# BLDC_PMSM.net
KiCad netlist of a schematic drawn in EAGLE
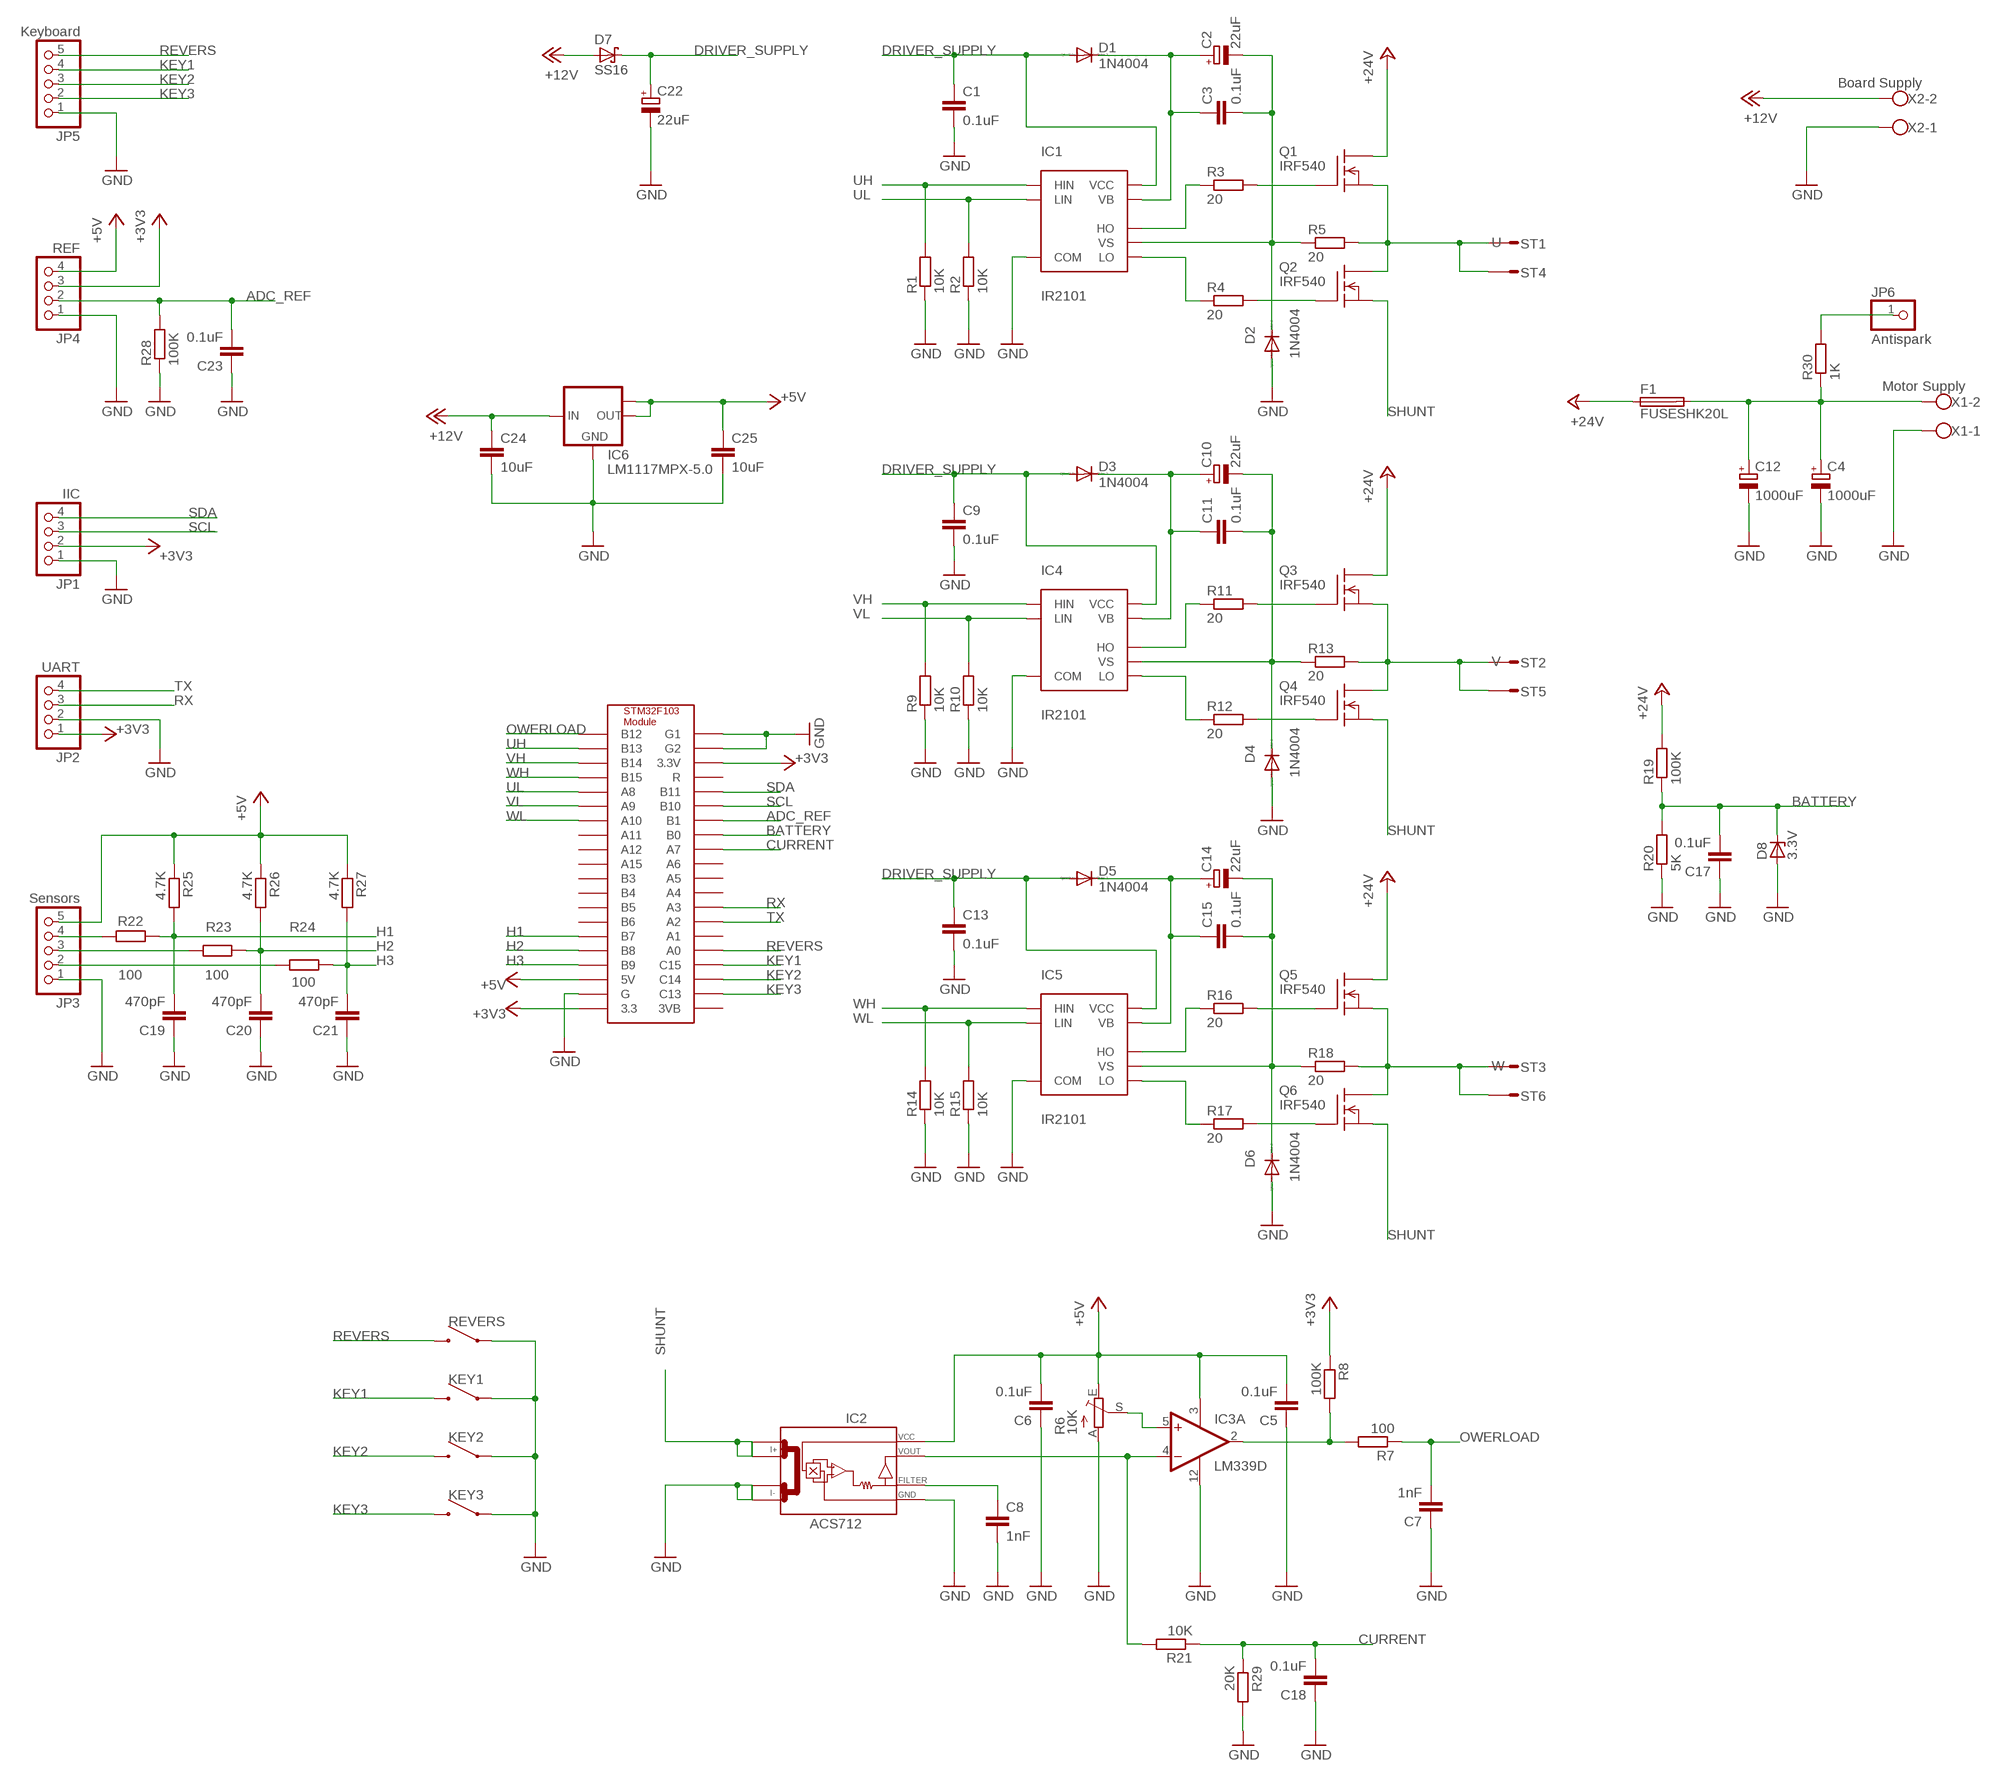
[diagram p0: schematic, sheet 1]

(export (version "E")
  (design (tool "Eeschema 10.0.6"))
  (components
    (comp (ref "C1")
      (value "0.1uF")
      (footprint "eagle-import:C0805K")
      (libsource (lib "eagle-import") (part "C-EUC0805K"))
    )
    (comp (ref "C2")
      (value "22uF")
      (footprint "eagle-import:E2-5")
      (libsource (lib "eagle-import") (part "CPOL-EUE2-5"))
    )
    (comp (ref "C3")
      (value "0.1uF")
      (footprint "eagle-import:C0805K")
      (libsource (lib "eagle-import") (part "C-EUC0805K"))
    )
    (comp (ref "C4")
      (value "1000uF")
      (footprint "eagle-import:E5-13")
      (libsource (lib "eagle-import") (part "CPOL-EUE5-13"))
    )
    (comp (ref "C5")
      (value "0.1uF")
      (footprint "eagle-import:C0805K")
      (libsource (lib "eagle-import") (part "C-EUC0805K"))
    )
    (comp (ref "C6")
      (value "0.1uF")
      (footprint "eagle-import:C0805K")
      (libsource (lib "eagle-import") (part "C-EUC0805K"))
    )
    (comp (ref "C7")
      (value "1nF")
      (footprint "eagle-import:C0805K")
      (libsource (lib "eagle-import") (part "C-EUC0805K"))
    )
    (comp (ref "C8")
      (value "1nF")
      (footprint "eagle-import:C0805K")
      (libsource (lib "eagle-import") (part "C-EUC0805K"))
    )
    (comp (ref "C9")
      (value "0.1uF")
      (footprint "eagle-import:C0805K")
      (libsource (lib "eagle-import") (part "C-EUC0805K"))
    )
    (comp (ref "C10")
      (value "22uF")
      (footprint "eagle-import:E2-5")
      (libsource (lib "eagle-import") (part "CPOL-EUE2-5"))
    )
    (comp (ref "C11")
      (value "0.1uF")
      (footprint "eagle-import:C0805K")
      (libsource (lib "eagle-import") (part "C-EUC0805K"))
    )
    (comp (ref "C12")
      (value "1000uF")
      (footprint "eagle-import:E5-13")
      (libsource (lib "eagle-import") (part "CPOL-EUE5-13"))
    )
    (comp (ref "C13")
      (value "0.1uF")
      (footprint "eagle-import:C0805K")
      (libsource (lib "eagle-import") (part "C-EUC0805K"))
    )
    (comp (ref "C14")
      (value "22uF")
      (footprint "eagle-import:E2-5")
      (libsource (lib "eagle-import") (part "CPOL-EUE2-5"))
    )
    (comp (ref "C15")
      (value "0.1uF")
      (footprint "eagle-import:C0805K")
      (libsource (lib "eagle-import") (part "C-EUC0805K"))
    )
    (comp (ref "C17")
      (value "0.1uF")
      (footprint "eagle-import:C0805K")
      (libsource (lib "eagle-import") (part "C-EUC0805K"))
    )
    (comp (ref "C18")
      (value "0.1uF")
      (footprint "eagle-import:C0805K")
      (libsource (lib "eagle-import") (part "C-EUC0805K"))
    )
    (comp (ref "C19")
      (value "470pF")
      (footprint "eagle-import:C0805K")
      (libsource (lib "eagle-import") (part "C-EUC0805K"))
    )
    (comp (ref "C20")
      (value "470pF")
      (footprint "eagle-import:C0805K")
      (libsource (lib "eagle-import") (part "C-EUC0805K"))
    )
    (comp (ref "C21")
      (value "470pF")
      (footprint "eagle-import:C0805K")
      (libsource (lib "eagle-import") (part "C-EUC0805K"))
    )
    (comp (ref "C22")
      (value "22uF")
      (footprint "eagle-import:E2-5")
      (libsource (lib "eagle-import") (part "CPOL-EUE2-5"))
    )
    (comp (ref "C23")
      (value "0.1uF")
      (footprint "eagle-import:C0805K")
      (libsource (lib "eagle-import") (part "C-EUC0805K"))
    )
    (comp (ref "C24")
      (value "10uF")
      (footprint "eagle-import:C0805K")
      (libsource (lib "eagle-import") (part "C-EUC0805K"))
    )
    (comp (ref "C25")
      (value "10uF")
      (footprint "eagle-import:C1206K")
      (libsource (lib "eagle-import") (part "C-EUC1206K"))
    )
    (comp (ref "D1")
      (value "1N4004")
      (footprint "eagle-import:DO41-10")
      (libsource (lib "eagle-import") (part "1N4004"))
    )
    (comp (ref "D2")
      (value "1N4004")
      (footprint "eagle-import:DO41-10")
      (libsource (lib "eagle-import") (part "1N4004"))
    )
    (comp (ref "D3")
      (value "1N4004")
      (footprint "eagle-import:DO41-10")
      (libsource (lib "eagle-import") (part "1N4004"))
    )
    (comp (ref "D4")
      (value "1N4004")
      (footprint "eagle-import:DO41-10")
      (libsource (lib "eagle-import") (part "1N4004"))
    )
    (comp (ref "D5")
      (value "1N4004")
      (footprint "eagle-import:DO41-10")
      (libsource (lib "eagle-import") (part "1N4004"))
    )
    (comp (ref "D6")
      (value "1N4004")
      (footprint "eagle-import:DO41-10")
      (libsource (lib "eagle-import") (part "1N4004"))
    )
    (comp (ref "D7")
      (value "SS16")
      (footprint "eagle-import:SMB")
      (libsource (lib "eagle-import") (part "SCHOTTKY-DIODESMD"))
    )
    (comp (ref "D8")
      (value "3.3V")
      (footprint "eagle-import:SMB")
      (libsource (lib "eagle-import") (part "ZENER-DIODESMB"))
    )
    (comp (ref "F1")
      (value "FUSESHK20L")
      (footprint "eagle-import:SHK20L")
      (libsource (lib "eagle-import") (part "FUSESHK20L"))
    )
    (comp (ref "IC1")
      (value "IR2101")
      (footprint "eagle-import:SO08")
      (libsource (lib "eagle-import") (part "IR2101S"))
    )
    (comp (ref "IC2")
      (value "ACS712")
      (footprint "eagle-import:SO08")
      (libsource (lib "eagle-import") (part "ACS712"))
    )
    (comp (ref "IC3")
      (value "LM339D")
      (footprint "eagle-import:SO14")
      (libsource (lib "eagle-import") (part "LM339D"))
    )
    (comp (ref "IC4")
      (value "IR2101")
      (footprint "eagle-import:SO08")
      (libsource (lib "eagle-import") (part "IR2101S"))
    )
    (comp (ref "IC5")
      (value "IR2101")
      (footprint "eagle-import:SO08")
      (libsource (lib "eagle-import") (part "IR2101S"))
    )
    (comp (ref "IC6")
      (value "LM1117MPX-5.0")
      (footprint "eagle-import:SOT223")
      (libsource (lib "eagle-import") (part "LM1117MPX-5.0"))
    )
    (comp (ref "JP1")
      (value "IIC")
      (footprint "eagle-import:1X04")
      (libsource (lib "eagle-import") (part "PINHD-1X4"))
    )
    (comp (ref "JP2")
      (value "UART")
      (footprint "eagle-import:1X04")
      (libsource (lib "eagle-import") (part "PINHD-1X4"))
    )
    (comp (ref "JP3")
      (value "Sensors")
      (footprint "eagle-import:1X05")
      (libsource (lib "eagle-import") (part "PINHD-1X5"))
    )
    (comp (ref "JP4")
      (value "REF")
      (footprint "eagle-import:1X04")
      (libsource (lib "eagle-import") (part "PINHD-1X4"))
    )
    (comp (ref "JP5")
      (value "Keyboard")
      (footprint "eagle-import:1X05")
      (libsource (lib "eagle-import") (part "PINHD-1X5"))
    )
    (comp (ref "JP6")
      (value "Antispark")
      (footprint "eagle-import:1X01")
      (libsource (lib "eagle-import") (part "PINHD-1X1"))
    )
    (comp (ref "KEY1")
      (value "SWITCH")
      (footprint "eagle-import:SWITCH")
      (libsource (lib "eagle-import") (part "SWITCH"))
    )
    (comp (ref "KEY2")
      (value "SWITCH")
      (footprint "eagle-import:SWITCH")
      (libsource (lib "eagle-import") (part "SWITCH"))
    )
    (comp (ref "KEY3")
      (value "SWITCH")
      (footprint "eagle-import:SWITCH")
      (libsource (lib "eagle-import") (part "SWITCH"))
    )
    (comp (ref "Q1")
      (value "IRF540")
      (footprint "eagle-import:TO220")
      (libsource (lib "eagle-import") (part "IRF540"))
    )
    (comp (ref "Q2")
      (value "IRF540")
      (footprint "eagle-import:TO220")
      (libsource (lib "eagle-import") (part "IRF540"))
    )
    (comp (ref "Q3")
      (value "IRF540")
      (footprint "eagle-import:TO220")
      (libsource (lib "eagle-import") (part "IRF540"))
    )
    (comp (ref "Q4")
      (value "IRF540")
      (footprint "eagle-import:TO220")
      (libsource (lib "eagle-import") (part "IRF540"))
    )
    (comp (ref "Q5")
      (value "IRF540")
      (footprint "eagle-import:TO220")
      (libsource (lib "eagle-import") (part "IRF540"))
    )
    (comp (ref "Q6")
      (value "IRF540")
      (footprint "eagle-import:TO220")
      (libsource (lib "eagle-import") (part "IRF540"))
    )
    (comp (ref "R1")
      (value "10K")
      (footprint "eagle-import:M0805")
      (libsource (lib "eagle-import") (part "R-EU_M0805"))
    )
    (comp (ref "R2")
      (value "10K")
      (footprint "eagle-import:M0805")
      (libsource (lib "eagle-import") (part "R-EU_M0805"))
    )
    (comp (ref "R3")
      (value "20")
      (footprint "eagle-import:M0805")
      (libsource (lib "eagle-import") (part "R-EU_M0805"))
    )
    (comp (ref "R4")
      (value "20")
      (footprint "eagle-import:M0805")
      (libsource (lib "eagle-import") (part "R-EU_M0805"))
    )
    (comp (ref "R5")
      (value "20")
      (footprint "eagle-import:M0805")
      (libsource (lib "eagle-import") (part "R-EU_M0805"))
    )
    (comp (ref "R6")
      (value "10K")
      (footprint "eagle-import:CA6V")
      (libsource (lib "eagle-import") (part "TRIM_EU-CA6V"))
    )
    (comp (ref "R7")
      (value "100")
      (footprint "eagle-import:M0805")
      (libsource (lib "eagle-import") (part "R-EU_M0805"))
    )
    (comp (ref "R8")
      (value "100K")
      (footprint "eagle-import:M0805")
      (libsource (lib "eagle-import") (part "R-EU_M0805"))
    )
    (comp (ref "R9")
      (value "10K")
      (footprint "eagle-import:M0805")
      (libsource (lib "eagle-import") (part "R-EU_M0805"))
    )
    (comp (ref "R10")
      (value "10K")
      (footprint "eagle-import:M0805")
      (libsource (lib "eagle-import") (part "R-EU_M0805"))
    )
    (comp (ref "R11")
      (value "20")
      (footprint "eagle-import:M0805")
      (libsource (lib "eagle-import") (part "R-EU_M0805"))
    )
    (comp (ref "R12")
      (value "20")
      (footprint "eagle-import:M0805")
      (libsource (lib "eagle-import") (part "R-EU_M0805"))
    )
    (comp (ref "R13")
      (value "20")
      (footprint "eagle-import:M0805")
      (libsource (lib "eagle-import") (part "R-EU_M0805"))
    )
    (comp (ref "R14")
      (value "10K")
      (footprint "eagle-import:M0805")
      (libsource (lib "eagle-import") (part "R-EU_M0805"))
    )
    (comp (ref "R15")
      (value "10K")
      (footprint "eagle-import:M0805")
      (libsource (lib "eagle-import") (part "R-EU_M0805"))
    )
    (comp (ref "R16")
      (value "20")
      (footprint "eagle-import:M0805")
      (libsource (lib "eagle-import") (part "R-EU_M0805"))
    )
    (comp (ref "R17")
      (value "20")
      (footprint "eagle-import:M0805")
      (libsource (lib "eagle-import") (part "R-EU_M0805"))
    )
    (comp (ref "R18")
      (value "20")
      (footprint "eagle-import:M0805")
      (libsource (lib "eagle-import") (part "R-EU_M0805"))
    )
    (comp (ref "R19")
      (value "100K")
      (footprint "eagle-import:M0805")
      (libsource (lib "eagle-import") (part "R-EU_M0805"))
    )
    (comp (ref "R20")
      (value "5K")
      (footprint "eagle-import:M0805")
      (libsource (lib "eagle-import") (part "R-EU_M0805"))
    )
    (comp (ref "R21")
      (value "10K")
      (footprint "eagle-import:M0805")
      (libsource (lib "eagle-import") (part "R-EU_M0805"))
    )
    (comp (ref "R22")
      (value "100")
      (footprint "eagle-import:M0805")
      (libsource (lib "eagle-import") (part "R-EU_M0805"))
    )
    (comp (ref "R23")
      (value "100")
      (footprint "eagle-import:M0805")
      (libsource (lib "eagle-import") (part "R-EU_M0805"))
    )
    (comp (ref "R24")
      (value "100")
      (footprint "eagle-import:M0805")
      (libsource (lib "eagle-import") (part "R-EU_M0805"))
    )
    (comp (ref "R25")
      (value "4.7K")
      (footprint "eagle-import:M0805")
      (libsource (lib "eagle-import") (part "R-EU_M0805"))
    )
    (comp (ref "R26")
      (value "4.7K")
      (footprint "eagle-import:M0805")
      (libsource (lib "eagle-import") (part "R-EU_M0805"))
    )
    (comp (ref "R27")
      (value "4.7K")
      (footprint "eagle-import:M0805")
      (libsource (lib "eagle-import") (part "R-EU_M0805"))
    )
    (comp (ref "R28")
      (value "100K")
      (footprint "eagle-import:M0805")
      (libsource (lib "eagle-import") (part "R-EU_M0805"))
    )
    (comp (ref "R29")
      (value "20K")
      (footprint "eagle-import:M0805")
      (libsource (lib "eagle-import") (part "R-EU_M0805"))
    )
    (comp (ref "R30")
      (value "1K")
      (footprint "eagle-import:M0805")
      (libsource (lib "eagle-import") (part "R-EU_M0805"))
    )
    (comp (ref "REVERS")
      (value "SWITCH")
      (footprint "eagle-import:SWITCH")
      (libsource (lib "eagle-import") (part "SWITCH"))
    )
    (comp (ref "ST1")
      (value "ST2,8")
      (footprint "eagle-import:ST2,8")
      (libsource (lib "eagle-import") (part "ST2,8"))
    )
    (comp (ref "ST2")
      (value "ST2,8")
      (footprint "eagle-import:ST2,8")
      (libsource (lib "eagle-import") (part "ST2,8"))
    )
    (comp (ref "ST3")
      (value "ST2,8")
      (footprint "eagle-import:ST2,8")
      (libsource (lib "eagle-import") (part "ST2,8"))
    )
    (comp (ref "ST4")
      (value "ST2,8")
      (footprint "eagle-import:ST2,8")
      (libsource (lib "eagle-import") (part "ST2,8"))
    )
    (comp (ref "ST5")
      (value "ST2,8")
      (footprint "eagle-import:ST2,8")
      (libsource (lib "eagle-import") (part "ST2,8"))
    )
    (comp (ref "ST6")
      (value "ST2,8")
      (footprint "eagle-import:ST2,8")
      (libsource (lib "eagle-import") (part "ST2,8"))
    )
    (comp (ref "U$1")
      (value "STM32F103MODULE")
      (footprint "eagle-import:STM32F103MODULE")
      (libsource (lib "eagle-import") (part "STM32F103MODULE"))
    )
    (comp (ref "X1")
      (value "Motor Supply")
      (footprint "eagle-import:W237-102")
      (fields (field (name "MPN") "237-102"))
      (libsource (lib "eagle-import") (part "W237-102"))
    )
    (comp (ref "X2")
      (value "Board Supply")
      (footprint "eagle-import:W237-102")
      (fields (field (name "MPN") "237-102"))
      (libsource (lib "eagle-import") (part "W237-102"))
    )
  )
  (nets
    (net (code "1") (name "+3V3") (class "Default")
      (node (ref "JP1") (pin "2") (pinfunction "2_2") (pintype "passive"))
      (node (ref "JP2") (pin "1") (pinfunction "1_1") (pintype "passive"))
      (node (ref "JP4") (pin "3") (pinfunction "3_3") (pintype "passive"))
      (node (ref "R8") (pin "1") (pinfunction "1_1") (pintype "passive"))
      (node (ref "U$1") (pin "P$20") (pinfunction "3.3_P$20") (pintype "power_in"))
      (node (ref "U$1") (pin "P$23") (pinfunction "3.3V_P$23") (pintype "power_in"))
    )
    (net (code "2") (name "+5V") (class "Default")
      (node (ref "C25") (pin "1") (pinfunction "1_1") (pintype "passive"))
      (node (ref "C5") (pin "2") (pinfunction "2_2") (pintype "passive"))
      (node (ref "C6") (pin "2") (pinfunction "2_2") (pintype "passive"))
      (node (ref "IC2") (pin "8") (pinfunction "VCC_8") (pintype "power_in"))
      (node (ref "IC3") (pin "3") (pinfunction "V+_3") (pintype "power_in"))
      (node (ref "IC6") (pin "2") (pinfunction "OUT_2") (pintype "passive"))
      (node (ref "IC6") (pin "TAB") (pinfunction "OUT1_TAB") (pintype "passive"))
      (node (ref "JP3") (pin "5") (pinfunction "5_5") (pintype "passive"))
      (node (ref "JP4") (pin "4") (pinfunction "4_4") (pintype "passive"))
      (node (ref "R25") (pin "1") (pinfunction "1_1") (pintype "passive"))
      (node (ref "R26") (pin "1") (pinfunction "1_1") (pintype "passive"))
      (node (ref "R27") (pin "1") (pinfunction "1_1") (pintype "passive"))
      (node (ref "R6") (pin "E") (pinfunction "E_E") (pintype "passive"))
      (node (ref "U$1") (pin "P$18") (pinfunction "5V_P$18") (pintype "power_in"))
    )
    (net (code "3") (name "+12V") (class "Default")
      (node (ref "C24") (pin "1") (pinfunction "1_1") (pintype "passive"))
      (node (ref "D7") (pin "A") (pinfunction "A_A") (pintype "passive"))
      (node (ref "IC6") (pin "3") (pinfunction "IN_3") (pintype "input"))
      (node (ref "X2") (pin "2") (pinfunction "KL_2") (pintype "passive"))
    )
    (net (code "4") (name "+24V") (class "Default")
      (node (ref "F1") (pin "1A") (pinfunction "1_1A") (pintype "passive"))
      (node (ref "Q1") (pin "2") (pinfunction "D_2") (pintype "passive"))
      (node (ref "Q3") (pin "2") (pinfunction "D_2") (pintype "passive"))
      (node (ref "Q5") (pin "2") (pinfunction "D_2") (pintype "passive"))
      (node (ref "R19") (pin "2") (pinfunction "2_2") (pintype "passive"))
    )
    (net (code "5") (name "/3VB") (class "Default")
      (node (ref "U$1") (pin "P$40") (pinfunction "3VB_P$40") (pintype "power_in"))
    )
    (net (code "6") (name "/ADC_REF") (class "Default")
      (node (ref "C23") (pin "2") (pinfunction "2_2") (pintype "passive"))
      (node (ref "JP4") (pin "2") (pinfunction "2_2") (pintype "passive"))
      (node (ref "R28") (pin "2") (pinfunction "2_2") (pintype "passive"))
      (node (ref "U$1") (pin "P$27") (pinfunction "B1_P$27") (pintype "bidirectional"))
    )
    (net (code "7") (name "/BATTERY") (class "Default")
      (node (ref "C17") (pin "2") (pinfunction "2_2") (pintype "passive"))
      (node (ref "D8") (pin "C") (pinfunction "C_C") (pintype "passive"))
      (node (ref "R19") (pin "1") (pinfunction "1_1") (pintype "passive"))
      (node (ref "R20") (pin "2") (pinfunction "2_2") (pintype "passive"))
      (node (ref "U$1") (pin "P$28") (pinfunction "B0_P$28") (pintype "bidirectional"))
    )
    (net (code "8") (name "/CURRENT") (class "Default")
      (node (ref "C18") (pin "2") (pinfunction "2_2") (pintype "passive"))
      (node (ref "R21") (pin "1") (pinfunction "1_1") (pintype "passive"))
      (node (ref "R29") (pin "1") (pinfunction "1_1") (pintype "passive"))
      (node (ref "U$1") (pin "P$29") (pinfunction "A7_P$29") (pintype "bidirectional"))
    )
    (net (code "9") (name "/DRIVER_SUPPLY") (class "Default")
      (node (ref "C1") (pin "1") (pinfunction "1_1") (pintype "passive"))
      (node (ref "C13") (pin "1") (pinfunction "1_1") (pintype "passive"))
      (node (ref "C22") (pin "+") (pinfunction "+_+") (pintype "passive"))
      (node (ref "C9") (pin "1") (pinfunction "1_1") (pintype "passive"))
      (node (ref "D1") (pin "A") (pinfunction "A_A") (pintype "passive"))
      (node (ref "D3") (pin "A") (pinfunction "A_A") (pintype "passive"))
      (node (ref "D5") (pin "A") (pinfunction "A_A") (pintype "passive"))
      (node (ref "D7") (pin "C") (pinfunction "C_C") (pintype "passive"))
      (node (ref "IC1") (pin "1") (pinfunction "VCC_1") (pintype "power_in"))
      (node (ref "IC4") (pin "1") (pinfunction "VCC_1") (pintype "power_in"))
      (node (ref "IC5") (pin "1") (pinfunction "VCC_1") (pintype "power_in"))
    )
    (net (code "10") (name "/H1") (class "Default")
      (node (ref "C19") (pin "2") (pinfunction "2_2") (pintype "passive"))
      (node (ref "R22") (pin "1") (pinfunction "1_1") (pintype "passive"))
      (node (ref "R25") (pin "2") (pinfunction "2_2") (pintype "passive"))
      (node (ref "U$1") (pin "P$15") (pinfunction "B7_P$15") (pintype "bidirectional"))
    )
    (net (code "11") (name "/H2") (class "Default")
      (node (ref "C20") (pin "2") (pinfunction "2_2") (pintype "passive"))
      (node (ref "R23") (pin "1") (pinfunction "1_1") (pintype "passive"))
      (node (ref "R26") (pin "2") (pinfunction "2_2") (pintype "passive"))
      (node (ref "U$1") (pin "P$16") (pinfunction "B8_P$16") (pintype "bidirectional"))
    )
    (net (code "12") (name "/H3") (class "Default")
      (node (ref "C21") (pin "2") (pinfunction "2_2") (pintype "passive"))
      (node (ref "R24") (pin "1") (pinfunction "1_1") (pintype "passive"))
      (node (ref "R27") (pin "2") (pinfunction "2_2") (pintype "passive"))
      (node (ref "U$1") (pin "P$17") (pinfunction "B9_P$17") (pintype "bidirectional"))
    )
    (net (code "13") (name "/KEY1") (class "Default")
      (node (ref "JP5") (pin "4") (pinfunction "4_4") (pintype "passive"))
      (node (ref "KEY1") (pin "P$1") (pinfunction "1_P$1") (pintype "passive"))
      (node (ref "U$1") (pin "P$37") (pinfunction "C15_P$37") (pintype "bidirectional"))
    )
    (net (code "14") (name "/KEY2") (class "Default")
      (node (ref "JP5") (pin "3") (pinfunction "3_3") (pintype "passive"))
      (node (ref "KEY2") (pin "P$1") (pinfunction "1_P$1") (pintype "passive"))
      (node (ref "U$1") (pin "P$38") (pinfunction "C14_P$38") (pintype "bidirectional"))
    )
    (net (code "15") (name "/KEY3") (class "Default")
      (node (ref "JP5") (pin "2") (pinfunction "2_2") (pintype "passive"))
      (node (ref "KEY3") (pin "P$1") (pinfunction "1_P$1") (pintype "passive"))
      (node (ref "U$1") (pin "P$39") (pinfunction "C13_P$39") (pintype "bidirectional"))
    )
    (net (code "16") (name "/OWERLOAD") (class "Default")
      (node (ref "C7") (pin "2") (pinfunction "2_2") (pintype "passive"))
      (node (ref "R7") (pin "1") (pinfunction "1_1") (pintype "passive"))
      (node (ref "U$1") (pin "P$1") (pinfunction "B12_P$1") (pintype "bidirectional"))
    )
    (net (code "17") (name "/REVERS") (class "Default")
      (node (ref "JP5") (pin "5") (pinfunction "5_5") (pintype "passive"))
      (node (ref "REVERS") (pin "P$1") (pinfunction "1_P$1") (pintype "passive"))
      (node (ref "U$1") (pin "P$36") (pinfunction "A0_P$36") (pintype "bidirectional"))
    )
    (net (code "18") (name "/RX") (class "Default")
      (node (ref "JP2") (pin "3") (pinfunction "3_3") (pintype "passive"))
      (node (ref "U$1") (pin "P$33") (pinfunction "A3_P$33") (pintype "bidirectional"))
    )
    (net (code "19") (name "/SCL") (class "Default")
      (node (ref "JP1") (pin "3") (pinfunction "3_3") (pintype "passive"))
      (node (ref "U$1") (pin "P$26") (pinfunction "B10_P$26") (pintype "bidirectional"))
    )
    (net (code "20") (name "/SDA") (class "Default")
      (node (ref "JP1") (pin "4") (pinfunction "4_4") (pintype "passive"))
      (node (ref "U$1") (pin "P$25") (pinfunction "B11_P$25") (pintype "bidirectional"))
    )
    (net (code "21") (name "/SHUNT") (class "Default")
      (node (ref "IC2") (pin "1") (pinfunction "I+_0_1") (pintype "bidirectional"))
      (node (ref "IC2") (pin "2") (pinfunction "I+_1_2") (pintype "bidirectional"))
      (node (ref "Q2") (pin "3") (pinfunction "S_3") (pintype "passive"))
      (node (ref "Q4") (pin "3") (pinfunction "S_3") (pintype "passive"))
      (node (ref "Q6") (pin "3") (pinfunction "S_3") (pintype "passive"))
    )
    (net (code "22") (name "/TX") (class "Default")
      (node (ref "JP2") (pin "4") (pinfunction "4_4") (pintype "passive"))
      (node (ref "U$1") (pin "P$34") (pinfunction "A2_P$34") (pintype "bidirectional"))
    )
    (net (code "23") (name "/U") (class "Default")
      (node (ref "Q1") (pin "3") (pinfunction "S_3") (pintype "passive"))
      (node (ref "Q2") (pin "2") (pinfunction "D_2") (pintype "passive"))
      (node (ref "R5") (pin "2") (pinfunction "2_2") (pintype "passive"))
      (node (ref "ST1") (pin "1") (pinfunction "ST_1") (pintype "passive"))
      (node (ref "ST4") (pin "1") (pinfunction "ST_1") (pintype "passive"))
    )
    (net (code "24") (name "/UH") (class "Default")
      (node (ref "IC1") (pin "2") (pinfunction "HIN_2") (pintype "bidirectional"))
      (node (ref "R1") (pin "2") (pinfunction "2_2") (pintype "passive"))
      (node (ref "U$1") (pin "P$2") (pinfunction "B13_P$2") (pintype "bidirectional"))
    )
    (net (code "25") (name "/UL") (class "Default")
      (node (ref "IC1") (pin "3") (pinfunction "LIN_3") (pintype "bidirectional"))
      (node (ref "R2") (pin "2") (pinfunction "2_2") (pintype "passive"))
      (node (ref "U$1") (pin "P$5") (pinfunction "A8_P$5") (pintype "bidirectional"))
    )
    (net (code "26") (name "/V") (class "Default")
      (node (ref "Q3") (pin "3") (pinfunction "S_3") (pintype "passive"))
      (node (ref "Q4") (pin "2") (pinfunction "D_2") (pintype "passive"))
      (node (ref "R13") (pin "2") (pinfunction "2_2") (pintype "passive"))
      (node (ref "ST2") (pin "1") (pinfunction "ST_1") (pintype "passive"))
      (node (ref "ST5") (pin "1") (pinfunction "ST_1") (pintype "passive"))
    )
    (net (code "27") (name "/VH") (class "Default")
      (node (ref "IC4") (pin "2") (pinfunction "HIN_2") (pintype "bidirectional"))
      (node (ref "R9") (pin "2") (pinfunction "2_2") (pintype "passive"))
      (node (ref "U$1") (pin "P$3") (pinfunction "B14_P$3") (pintype "bidirectional"))
    )
    (net (code "28") (name "/VL") (class "Default")
      (node (ref "IC4") (pin "3") (pinfunction "LIN_3") (pintype "bidirectional"))
      (node (ref "R10") (pin "2") (pinfunction "2_2") (pintype "passive"))
      (node (ref "U$1") (pin "P$6") (pinfunction "A9_P$6") (pintype "bidirectional"))
    )
    (net (code "29") (name "/W") (class "Default")
      (node (ref "Q5") (pin "3") (pinfunction "S_3") (pintype "passive"))
      (node (ref "Q6") (pin "2") (pinfunction "D_2") (pintype "passive"))
      (node (ref "R18") (pin "2") (pinfunction "2_2") (pintype "passive"))
      (node (ref "ST3") (pin "1") (pinfunction "ST_1") (pintype "passive"))
      (node (ref "ST6") (pin "1") (pinfunction "ST_1") (pintype "passive"))
    )
    (net (code "30") (name "/WH") (class "Default")
      (node (ref "IC5") (pin "2") (pinfunction "HIN_2") (pintype "bidirectional"))
      (node (ref "R14") (pin "2") (pinfunction "2_2") (pintype "passive"))
      (node (ref "U$1") (pin "P$4") (pinfunction "B15_P$4") (pintype "bidirectional"))
    )
    (net (code "31") (name "/WL") (class "Default")
      (node (ref "IC5") (pin "3") (pinfunction "LIN_3") (pintype "bidirectional"))
      (node (ref "R15") (pin "2") (pinfunction "2_2") (pintype "passive"))
      (node (ref "U$1") (pin "P$7") (pinfunction "A10_P$7") (pintype "bidirectional"))
    )
    (net (code "32") (name "GND") (class "Default")
      (node (ref "C1") (pin "2") (pinfunction "2_2") (pintype "passive"))
      (node (ref "C12") (pin "-") (pinfunction "-_-") (pintype "passive"))
      (node (ref "C13") (pin "2") (pinfunction "2_2") (pintype "passive"))
      (node (ref "C17") (pin "1") (pinfunction "1_1") (pintype "passive"))
      (node (ref "C18") (pin "1") (pinfunction "1_1") (pintype "passive"))
      (node (ref "C19") (pin "1") (pinfunction "1_1") (pintype "passive"))
      (node (ref "C20") (pin "1") (pinfunction "1_1") (pintype "passive"))
      (node (ref "C21") (pin "1") (pinfunction "1_1") (pintype "passive"))
      (node (ref "C22") (pin "-") (pinfunction "-_-") (pintype "passive"))
      (node (ref "C23") (pin "1") (pinfunction "1_1") (pintype "passive"))
      (node (ref "C24") (pin "2") (pinfunction "2_2") (pintype "passive"))
      (node (ref "C25") (pin "2") (pinfunction "2_2") (pintype "passive"))
      (node (ref "C4") (pin "-") (pinfunction "-_-") (pintype "passive"))
      (node (ref "C5") (pin "1") (pinfunction "1_1") (pintype "passive"))
      (node (ref "C6") (pin "1") (pinfunction "1_1") (pintype "passive"))
      (node (ref "C7") (pin "1") (pinfunction "1_1") (pintype "passive"))
      (node (ref "C8") (pin "2") (pinfunction "2_2") (pintype "passive"))
      (node (ref "C9") (pin "2") (pinfunction "2_2") (pintype "passive"))
      (node (ref "D2") (pin "A") (pinfunction "A_A") (pintype "passive"))
      (node (ref "D4") (pin "A") (pinfunction "A_A") (pintype "passive"))
      (node (ref "D6") (pin "A") (pinfunction "A_A") (pintype "passive"))
      (node (ref "D8") (pin "A") (pinfunction "A_A") (pintype "passive"))
      (node (ref "IC1") (pin "4") (pinfunction "COM_4") (pintype "power_in"))
      (node (ref "IC2") (pin "3") (pinfunction "I-_0_3") (pintype "bidirectional"))
      (node (ref "IC2") (pin "4") (pinfunction "I-_1_4") (pintype "bidirectional"))
      (node (ref "IC2") (pin "5") (pinfunction "GND_5") (pintype "power_in"))
      (node (ref "IC3") (pin "12") (pinfunction "GND_12") (pintype "power_in"))
      (node (ref "IC4") (pin "4") (pinfunction "COM_4") (pintype "power_in"))
      (node (ref "IC5") (pin "4") (pinfunction "COM_4") (pintype "power_in"))
      (node (ref "IC6") (pin "1") (pinfunction "GND_1") (pintype "input"))
      (node (ref "JP1") (pin "1") (pinfunction "1_1") (pintype "passive"))
      (node (ref "JP2") (pin "2") (pinfunction "2_2") (pintype "passive"))
      (node (ref "JP3") (pin "1") (pinfunction "1_1") (pintype "passive"))
      (node (ref "JP4") (pin "1") (pinfunction "1_1") (pintype "passive"))
      (node (ref "JP5") (pin "1") (pinfunction "1_1") (pintype "passive"))
      (node (ref "KEY1") (pin "P$2") (pinfunction "2_P$2") (pintype "passive"))
      (node (ref "KEY2") (pin "P$2") (pinfunction "2_P$2") (pintype "passive"))
      (node (ref "KEY3") (pin "P$2") (pinfunction "2_P$2") (pintype "passive"))
      (node (ref "R1") (pin "1") (pinfunction "1_1") (pintype "passive"))
      (node (ref "R10") (pin "1") (pinfunction "1_1") (pintype "passive"))
      (node (ref "R14") (pin "1") (pinfunction "1_1") (pintype "passive"))
      (node (ref "R15") (pin "1") (pinfunction "1_1") (pintype "passive"))
      (node (ref "R2") (pin "1") (pinfunction "1_1") (pintype "passive"))
      (node (ref "R20") (pin "1") (pinfunction "1_1") (pintype "passive"))
      (node (ref "R28") (pin "1") (pinfunction "1_1") (pintype "passive"))
      (node (ref "R29") (pin "2") (pinfunction "2_2") (pintype "passive"))
      (node (ref "R6") (pin "A") (pinfunction "A_A") (pintype "passive"))
      (node (ref "R9") (pin "1") (pinfunction "1_1") (pintype "passive"))
      (node (ref "REVERS") (pin "P$2") (pinfunction "2_P$2") (pintype "passive"))
      (node (ref "U$1") (pin "P$19") (pinfunction "G_P$19") (pintype "power_in"))
      (node (ref "U$1") (pin "P$21") (pinfunction "G1_P$21") (pintype "power_in"))
      (node (ref "U$1") (pin "P$22") (pinfunction "G2_P$22") (pintype "power_in"))
      (node (ref "X1") (pin "1") (pinfunction "KL_1") (pintype "passive"))
      (node (ref "X2") (pin "1") (pinfunction "KL_1") (pintype "passive"))
    )
    (net (code "33") (name "Net-(F1-2)") (class "Default")
      (node (ref "C12") (pin "+") (pinfunction "+_+") (pintype "passive"))
      (node (ref "C4") (pin "+") (pinfunction "+_+") (pintype "passive"))
      (node (ref "F1") (pin "2A") (pinfunction "2_2A") (pintype "passive"))
      (node (ref "R30") (pin "1") (pinfunction "1_1") (pintype "passive"))
      (node (ref "X1") (pin "2") (pinfunction "KL_2") (pintype "passive"))
    )
    (net (code "34") (name "Net-(IC1-HO)") (class "Default")
      (node (ref "IC1") (pin "7") (pinfunction "HO_7") (pintype "bidirectional"))
      (node (ref "R3") (pin "1") (pinfunction "1_1") (pintype "passive"))
    )
    (net (code "35") (name "Net-(IC1-LO)") (class "Default")
      (node (ref "IC1") (pin "5") (pinfunction "LO_5") (pintype "bidirectional"))
      (node (ref "R4") (pin "1") (pinfunction "1_1") (pintype "passive"))
    )
    (net (code "36") (name "Net-(IC1-VB)") (class "Default")
      (node (ref "C2") (pin "+") (pinfunction "+_+") (pintype "passive"))
      (node (ref "C3") (pin "1") (pinfunction "1_1") (pintype "passive"))
      (node (ref "D1") (pin "C") (pinfunction "C_C") (pintype "passive"))
      (node (ref "IC1") (pin "8") (pinfunction "VB_8") (pintype "bidirectional"))
    )
    (net (code "37") (name "Net-(IC1-VS)") (class "Default")
      (node (ref "C2") (pin "-") (pinfunction "-_-") (pintype "passive"))
      (node (ref "C3") (pin "2") (pinfunction "2_2") (pintype "passive"))
      (node (ref "D2") (pin "C") (pinfunction "C_C") (pintype "passive"))
      (node (ref "IC1") (pin "6") (pinfunction "VS_6") (pintype "bidirectional"))
      (node (ref "R5") (pin "1") (pinfunction "1_1") (pintype "passive"))
    )
    (net (code "38") (name "Net-(IC2-FILTER)") (class "Default")
      (node (ref "C8") (pin "1") (pinfunction "1_1") (pintype "passive"))
      (node (ref "IC2") (pin "6") (pinfunction "FILTER_6") (pintype "bidirectional"))
    )
    (net (code "39") (name "Net-(IC2-VOUT)") (class "Default")
      (node (ref "IC2") (pin "7") (pinfunction "VOUT_7") (pintype "output"))
      (node (ref "IC3") (pin "4") (pinfunction "-IN_4") (pintype "input"))
      (node (ref "R21") (pin "2") (pinfunction "2_2") (pintype "passive"))
    )
    (net (code "40") (name "Net-(IC3A-+IN)") (class "Default")
      (node (ref "IC3") (pin "5") (pinfunction "+IN_5") (pintype "input"))
      (node (ref "R6") (pin "S") (pinfunction "S_S") (pintype "passive"))
    )
    (net (code "41") (name "Net-(IC3A-OUT)") (class "Default")
      (node (ref "IC3") (pin "2") (pinfunction "OUT_2") (pintype "open_collector"))
      (node (ref "R7") (pin "2") (pinfunction "2_2") (pintype "passive"))
      (node (ref "R8") (pin "2") (pinfunction "2_2") (pintype "passive"))
    )
    (net (code "42") (name "Net-(IC4-HO)") (class "Default")
      (node (ref "IC4") (pin "7") (pinfunction "HO_7") (pintype "bidirectional"))
      (node (ref "R11") (pin "1") (pinfunction "1_1") (pintype "passive"))
    )
    (net (code "43") (name "Net-(IC4-LO)") (class "Default")
      (node (ref "IC4") (pin "5") (pinfunction "LO_5") (pintype "bidirectional"))
      (node (ref "R12") (pin "1") (pinfunction "1_1") (pintype "passive"))
    )
    (net (code "44") (name "Net-(IC4-VB)") (class "Default")
      (node (ref "C10") (pin "+") (pinfunction "+_+") (pintype "passive"))
      (node (ref "C11") (pin "1") (pinfunction "1_1") (pintype "passive"))
      (node (ref "D3") (pin "C") (pinfunction "C_C") (pintype "passive"))
      (node (ref "IC4") (pin "8") (pinfunction "VB_8") (pintype "bidirectional"))
    )
    (net (code "45") (name "Net-(IC4-VS)") (class "Default")
      (node (ref "C10") (pin "-") (pinfunction "-_-") (pintype "passive"))
      (node (ref "C11") (pin "2") (pinfunction "2_2") (pintype "passive"))
      (node (ref "D4") (pin "C") (pinfunction "C_C") (pintype "passive"))
      (node (ref "IC4") (pin "6") (pinfunction "VS_6") (pintype "bidirectional"))
      (node (ref "R13") (pin "1") (pinfunction "1_1") (pintype "passive"))
    )
    (net (code "46") (name "Net-(IC5-HO)") (class "Default")
      (node (ref "IC5") (pin "7") (pinfunction "HO_7") (pintype "bidirectional"))
      (node (ref "R16") (pin "1") (pinfunction "1_1") (pintype "passive"))
    )
    (net (code "47") (name "Net-(IC5-LO)") (class "Default")
      (node (ref "IC5") (pin "5") (pinfunction "LO_5") (pintype "bidirectional"))
      (node (ref "R17") (pin "1") (pinfunction "1_1") (pintype "passive"))
    )
    (net (code "48") (name "Net-(IC5-VB)") (class "Default")
      (node (ref "C14") (pin "+") (pinfunction "+_+") (pintype "passive"))
      (node (ref "C15") (pin "1") (pinfunction "1_1") (pintype "passive"))
      (node (ref "D5") (pin "C") (pinfunction "C_C") (pintype "passive"))
      (node (ref "IC5") (pin "8") (pinfunction "VB_8") (pintype "bidirectional"))
    )
    (net (code "49") (name "Net-(IC5-VS)") (class "Default")
      (node (ref "C14") (pin "-") (pinfunction "-_-") (pintype "passive"))
      (node (ref "C15") (pin "2") (pinfunction "2_2") (pintype "passive"))
      (node (ref "D6") (pin "C") (pinfunction "C_C") (pintype "passive"))
      (node (ref "IC5") (pin "6") (pinfunction "VS_6") (pintype "bidirectional"))
      (node (ref "R18") (pin "1") (pinfunction "1_1") (pintype "passive"))
    )
    (net (code "50") (name "Net-(JP3-Pad2)") (class "Default")
      (node (ref "JP3") (pin "2") (pinfunction "2_2") (pintype "passive"))
      (node (ref "R24") (pin "2") (pinfunction "2_2") (pintype "passive"))
    )
    (net (code "51") (name "Net-(JP3-Pad3)") (class "Default")
      (node (ref "JP3") (pin "3") (pinfunction "3_3") (pintype "passive"))
      (node (ref "R23") (pin "2") (pinfunction "2_2") (pintype "passive"))
    )
    (net (code "52") (name "Net-(JP3-Pad4)") (class "Default")
      (node (ref "JP3") (pin "4") (pinfunction "4_4") (pintype "passive"))
      (node (ref "R22") (pin "2") (pinfunction "2_2") (pintype "passive"))
    )
    (net (code "53") (name "Net-(JP6-Pad1)") (class "Default")
      (node (ref "JP6") (pin "1") (pinfunction "1_1") (pintype "passive"))
      (node (ref "R30") (pin "2") (pinfunction "2_2") (pintype "passive"))
    )
    (net (code "54") (name "Net-(Q1-G)") (class "Default")
      (node (ref "Q1") (pin "1") (pinfunction "G_1") (pintype "passive"))
      (node (ref "R3") (pin "2") (pinfunction "2_2") (pintype "passive"))
    )
    (net (code "55") (name "Net-(Q2-G)") (class "Default")
      (node (ref "Q2") (pin "1") (pinfunction "G_1") (pintype "passive"))
      (node (ref "R4") (pin "2") (pinfunction "2_2") (pintype "passive"))
    )
    (net (code "56") (name "Net-(Q3-G)") (class "Default")
      (node (ref "Q3") (pin "1") (pinfunction "G_1") (pintype "passive"))
      (node (ref "R11") (pin "2") (pinfunction "2_2") (pintype "passive"))
    )
    (net (code "57") (name "Net-(Q4-G)") (class "Default")
      (node (ref "Q4") (pin "1") (pinfunction "G_1") (pintype "passive"))
      (node (ref "R12") (pin "2") (pinfunction "2_2") (pintype "passive"))
    )
    (net (code "58") (name "Net-(Q5-G)") (class "Default")
      (node (ref "Q5") (pin "1") (pinfunction "G_1") (pintype "passive"))
      (node (ref "R16") (pin "2") (pinfunction "2_2") (pintype "passive"))
    )
    (net (code "59") (name "Net-(Q6-G)") (class "Default")
      (node (ref "Q6") (pin "1") (pinfunction "G_1") (pintype "passive"))
      (node (ref "R17") (pin "2") (pinfunction "2_2") (pintype "passive"))
    )
    (net (code "60") (name "unconnected-(U$1-A1-PadP$35)") (class "Default")
      (node (ref "U$1") (pin "P$35") (pinfunction "A1_P$35") (pintype "bidirectional"))
    )
    (net (code "61") (name "unconnected-(U$1-A4-PadP$32)") (class "Default")
      (node (ref "U$1") (pin "P$32") (pinfunction "A4_P$32") (pintype "bidirectional"))
    )
    (net (code "62") (name "unconnected-(U$1-A5-PadP$31)") (class "Default")
      (node (ref "U$1") (pin "P$31") (pinfunction "A5_P$31") (pintype "bidirectional"))
    )
    (net (code "63") (name "unconnected-(U$1-A6-PadP$30)") (class "Default")
      (node (ref "U$1") (pin "P$30") (pinfunction "A6_P$30") (pintype "bidirectional"))
    )
    (net (code "64") (name "unconnected-(U$1-A11-PadP$8)") (class "Default")
      (node (ref "U$1") (pin "P$8") (pinfunction "A11_P$8") (pintype "bidirectional"))
    )
    (net (code "65") (name "unconnected-(U$1-A12-PadP$9)") (class "Default")
      (node (ref "U$1") (pin "P$9") (pinfunction "A12_P$9") (pintype "bidirectional"))
    )
    (net (code "66") (name "unconnected-(U$1-A15-PadP$10)") (class "Default")
      (node (ref "U$1") (pin "P$10") (pinfunction "A15_P$10") (pintype "bidirectional"))
    )
    (net (code "67") (name "unconnected-(U$1-B3-PadP$11)") (class "Default")
      (node (ref "U$1") (pin "P$11") (pinfunction "B3_P$11") (pintype "bidirectional"))
    )
    (net (code "68") (name "unconnected-(U$1-B4-PadP$12)") (class "Default")
      (node (ref "U$1") (pin "P$12") (pinfunction "B4_P$12") (pintype "bidirectional"))
    )
    (net (code "69") (name "unconnected-(U$1-B5-PadP$13)") (class "Default")
      (node (ref "U$1") (pin "P$13") (pinfunction "B5_P$13") (pintype "bidirectional"))
    )
    (net (code "70") (name "unconnected-(U$1-B6-PadP$14)") (class "Default")
      (node (ref "U$1") (pin "P$14") (pinfunction "B6_P$14") (pintype "bidirectional"))
    )
    (net (code "71") (name "unconnected-(U$1-R-PadP$24)") (class "Default")
      (node (ref "U$1") (pin "P$24") (pinfunction "R_P$24") (pintype "bidirectional"))
    )
  )
)
